# Magnetic_Direction_Sensor.net
KiCad netlist of a schematic drawn in EAGLE
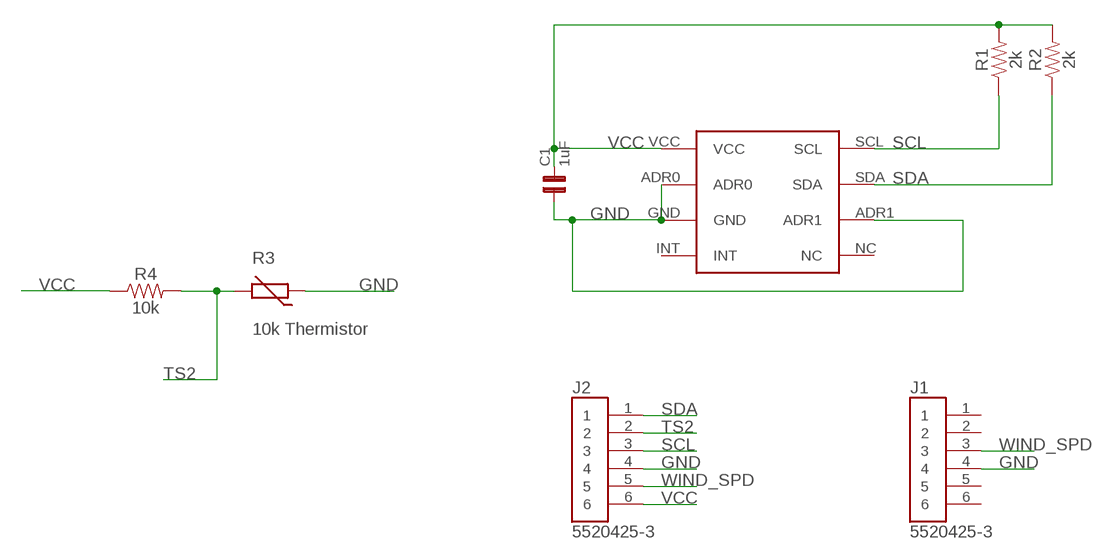
[diagram p0: schematic, sheet 1]

(export (version "E")
  (design (tool "Eeschema 10.0.6"))
  (components
    (comp (ref "C1")
      (value "1uF")
      (footprint "eagle-import:0805")
      (libsource (lib "eagle-import") (part "C0805"))
    )
    (comp (ref "J1")
      (value "5520425-3")
      (footprint "eagle-import:TE_5520425-3")
      (fields (field (name "DIGI-KEY_PART_NUMBER") "A31415-ND") (field (name "MF") "TE Connectivity"))
      (libsource (lib "eagle-import") (part "5520425-3"))
    )
    (comp (ref "J2")
      (value "5520425-3")
      (footprint "eagle-import:TE_5520425-3")
      (fields (field (name "DIGI-KEY_PART_NUMBER") "A31415-ND") (field (name "MF") "TE Connectivity"))
      (libsource (lib "eagle-import") (part "5520425-3"))
    )
    (comp (ref "R1")
      (value "2k")
      (footprint "eagle-import:0805")
      (libsource (lib "eagle-import") (part "RESISTOR0805"))
    )
    (comp (ref "R2")
      (value "2k")
      (footprint "eagle-import:0805")
      (libsource (lib "eagle-import") (part "RESISTOR0805"))
    )
    (comp (ref "R3")
      (value "10k Thermistor")
      (footprint "eagle-import:R-5")
      (libsource (lib "eagle-import") (part "THERMISTOR-5"))
    )
    (comp (ref "R4")
      (value "10k")
      (footprint "eagle-import:0805")
      (libsource (lib "eagle-import") (part "RESISTOR0805"))
    )
    (comp (ref "U$1")
      (value "ALS31313")
      (footprint "eagle-import:ALS31313-500")
      (libsource (lib "eagle-import") (part "ALS31313"))
    )
  )
  (nets
    (net (code "1") (name "/GND") (class "Default")
      (node (ref "C1") (pin "1") (pinfunction "1_1") (pintype "passive"))
      (node (ref "J1") (pin "4") (pinfunction "4_4") (pintype "passive"))
      (node (ref "J2") (pin "4") (pinfunction "4_4") (pintype "passive"))
      (node (ref "R3") (pin "1") (pinfunction "1_1") (pintype "passive"))
      (node (ref "U$1") (pin "ADR0") (pinfunction "ADR0_ADR0") (pintype "input"))
      (node (ref "U$1") (pin "ADR1") (pinfunction "ADR1_ADR1") (pintype "input"))
      (node (ref "U$1") (pin "GND") (pinfunction "GND_GND") (pintype "power_in"))
    )
    (net (code "2") (name "/SCL") (class "Default")
      (node (ref "J2") (pin "3") (pinfunction "3_3") (pintype "passive"))
      (node (ref "R1") (pin "1") (pinfunction "1_1") (pintype "passive"))
      (node (ref "U$1") (pin "SCL") (pinfunction "SCL_SCL") (pintype "input"))
    )
    (net (code "3") (name "/SDA") (class "Default")
      (node (ref "J2") (pin "1") (pinfunction "1_1") (pintype "passive"))
      (node (ref "R2") (pin "1") (pinfunction "1_1") (pintype "passive"))
      (node (ref "U$1") (pin "SDA") (pinfunction "SDA_SDA") (pintype "bidirectional"))
    )
    (net (code "4") (name "/TS2") (class "Default")
      (node (ref "J2") (pin "2") (pinfunction "2_2") (pintype "passive"))
      (node (ref "R3") (pin "2") (pinfunction "2_2") (pintype "passive"))
      (node (ref "R4") (pin "2") (pinfunction "2_2") (pintype "passive"))
    )
    (net (code "5") (name "/VCC") (class "Default")
      (node (ref "C1") (pin "2") (pinfunction "2_2") (pintype "passive"))
      (node (ref "J2") (pin "6") (pinfunction "6_6") (pintype "passive"))
      (node (ref "R1") (pin "2") (pinfunction "2_2") (pintype "passive"))
      (node (ref "R2") (pin "2") (pinfunction "2_2") (pintype "passive"))
      (node (ref "R4") (pin "1") (pinfunction "1_1") (pintype "passive"))
      (node (ref "U$1") (pin "VCC") (pinfunction "VCC_VCC") (pintype "power_in"))
    )
    (net (code "6") (name "/WIND_SPD") (class "Default")
      (node (ref "J1") (pin "3") (pinfunction "3_3") (pintype "passive"))
      (node (ref "J2") (pin "5") (pinfunction "5_5") (pintype "passive"))
    )
    (net (code "7") (name "unconnected-(J1-Pad1)") (class "Default")
      (node (ref "J1") (pin "1") (pinfunction "1_1") (pintype "passive"))
    )
    (net (code "8") (name "unconnected-(J1-Pad2)") (class "Default")
      (node (ref "J1") (pin "2") (pinfunction "2_2") (pintype "passive"))
    )
    (net (code "9") (name "unconnected-(J1-Pad5)") (class "Default")
      (node (ref "J1") (pin "5") (pinfunction "5_5") (pintype "passive"))
    )
    (net (code "10") (name "unconnected-(J1-Pad6)") (class "Default")
      (node (ref "J1") (pin "6") (pinfunction "6_6") (pintype "passive"))
    )
    (net (code "11") (name "unconnected-(U$1-PadINT)") (class "Default")
      (node (ref "U$1") (pin "INT") (pinfunction "INT_INT") (pintype "output"))
    )
    (net (code "12") (name "unconnected-(U$1-PadNC)") (class "Default")
      (node (ref "U$1") (pin "NC") (pinfunction "NC_NC") (pintype "no_connect"))
    )
  )
)
